# 1_Power_Switches.net
KiCad netlist of a schematic drawn in Altium Designer
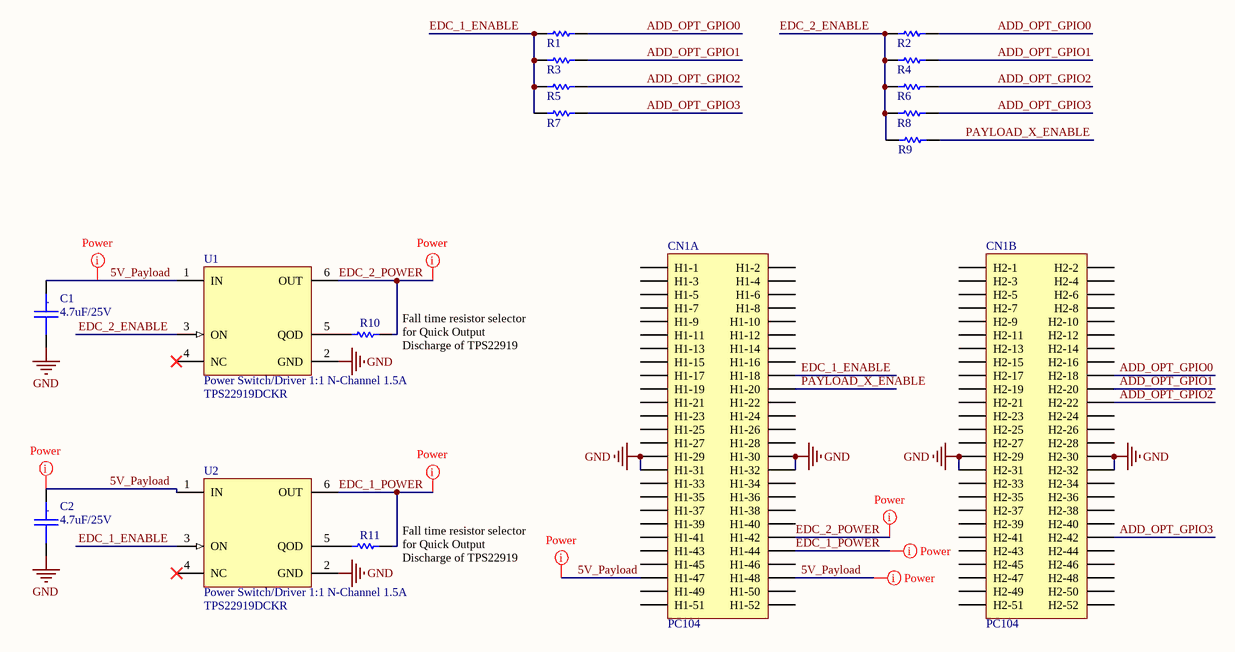
[diagram p0: 1_Power_Switches.SchDoc]

(export (version "E")
  (design (tool "Eeschema 10.0.6"))
  (components
    (comp (ref "C1")
      (value "4.7uF/25V")
      (footprint "C0805_MD")
      (fields
        (field (name "MANUFACTURER") "TDK")
        (field (name "MANUFACTURER PART NUMBER") "C2012X7R1E475K125AB")
        (field (name "TOLERANCE") "10%")
      )
      (libsource (lib "EDC_Power_Adapter") (part "C2012X7R1E475K125AB"))
    )
    (comp (ref "C2")
      (value "4.7uF/25V")
      (footprint "C0805_MD")
      (fields
        (field (name "MANUFACTURER") "TDK")
        (field (name "MANUFACTURER PART NUMBER") "C2012X7R1E475K125AB")
        (field (name "TOLERANCE") "10%")
      )
      (libsource (lib "EDC_Power_Adapter") (part "C2012X7R1E475K125AB"))
    )
    (comp (ref "CN1")
      (value "PC104")
      (footprint "PC104_ESQ-126-39-G-D")
      (description "Conn Elevated Socket SKT 52 POS 2.54mm Solder ST Thru-Hole Tube")
      (fields (field (name "PARTNUMBER") "ESQ-126-39-G-D") (field (name "MANUFACTURER") "Samtec"))
      (libsource (lib "EDC_Power_Adapter") (part "PC104_ESQ-126-39-G-D"))
    )
    (comp (ref "R1")
      (value "Optional 0805 resistor")
      (footprint "R0805_MD")
      (fields
        (field (name "MANUFACTURER") "Vishay")
        (field (name "MANUFACTURER PART NUMBER") "CRCW08050000Z0EA")
        (field (name "TOLERANCE") "1%")
      )
      (libsource (lib "EDC_Power_Adapter") (part "CRCW08050000Z0EA"))
    )
    (comp (ref "R2")
      (value "Optional 0805 resistor")
      (footprint "R0805_MD")
      (fields
        (field (name "MANUFACTURER") "Vishay")
        (field (name "MANUFACTURER PART NUMBER") "CRCW08050000Z0EA")
        (field (name "TOLERANCE") "1%")
      )
      (libsource (lib "EDC_Power_Adapter") (part "CRCW08050000Z0EA"))
    )
    (comp (ref "R3")
      (value "Optional 0805 resistor")
      (footprint "R0805_MD")
      (fields
        (field (name "MANUFACTURER") "Vishay")
        (field (name "MANUFACTURER PART NUMBER") "CRCW08050000Z0EA")
        (field (name "TOLERANCE") "1%")
      )
      (libsource (lib "EDC_Power_Adapter") (part "CRCW08050000Z0EA"))
    )
    (comp (ref "R4")
      (value "Optional 0805 resistor")
      (footprint "R0805_MD")
      (fields
        (field (name "MANUFACTURER") "Vishay")
        (field (name "MANUFACTURER PART NUMBER") "CRCW08050000Z0EA")
        (field (name "TOLERANCE") "1%")
      )
      (libsource (lib "EDC_Power_Adapter") (part "CRCW08050000Z0EA"))
    )
    (comp (ref "R5")
      (value "Optional 0805 resistor")
      (footprint "R0805_MD")
      (fields
        (field (name "MANUFACTURER") "Vishay")
        (field (name "MANUFACTURER PART NUMBER") "CRCW08050000Z0EA")
        (field (name "TOLERANCE") "1%")
      )
      (libsource (lib "EDC_Power_Adapter") (part "CRCW08050000Z0EA"))
    )
    (comp (ref "R6")
      (value "Optional 0805 resistor")
      (footprint "R0805_MD")
      (fields
        (field (name "MANUFACTURER") "Vishay")
        (field (name "MANUFACTURER PART NUMBER") "CRCW08050000Z0EA")
        (field (name "TOLERANCE") "1%")
      )
      (libsource (lib "EDC_Power_Adapter") (part "CRCW08050000Z0EA"))
    )
    (comp (ref "R7")
      (value "Optional 0805 resistor")
      (footprint "R0805_MD")
      (fields
        (field (name "MANUFACTURER") "Vishay")
        (field (name "MANUFACTURER PART NUMBER") "CRCW08050000Z0EA")
        (field (name "TOLERANCE") "1%")
      )
      (libsource (lib "EDC_Power_Adapter") (part "CRCW08050000Z0EA"))
    )
    (comp (ref "R8")
      (value "Optional 0805 resistor")
      (footprint "R0805_MD")
      (fields
        (field (name "MANUFACTURER") "Vishay")
        (field (name "MANUFACTURER PART NUMBER") "CRCW08050000Z0EA")
        (field (name "TOLERANCE") "1%")
      )
      (libsource (lib "EDC_Power_Adapter") (part "CRCW08050000Z0EA"))
    )
    (comp (ref "R9")
      (value "Optional 0805 resistor")
      (footprint "R0805_MD")
      (fields
        (field (name "MANUFACTURER") "Vishay")
        (field (name "MANUFACTURER PART NUMBER") "CRCW08050000Z0EA")
        (field (name "TOLERANCE") "1%")
      )
      (libsource (lib "EDC_Power_Adapter") (part "CRCW08050000Z0EA"))
    )
    (comp (ref "R10")
      (value "Optional 0805 resistor")
      (footprint "R0805_MD")
      (fields
        (field (name "MANUFACTURER") "Vishay")
        (field (name "MANUFACTURER PART NUMBER") "CRCW08050000Z0EA")
        (field (name "TOLERANCE") "1%")
      )
      (libsource (lib "EDC_Power_Adapter") (part "CRCW08050000Z0EA"))
    )
    (comp (ref "R11")
      (value "Optional 0805 resistor")
      (footprint "R0805_MD")
      (fields
        (field (name "MANUFACTURER") "Vishay")
        (field (name "MANUFACTURER PART NUMBER") "CRCW08050000Z0EA")
        (field (name "TOLERANCE") "1%")
      )
      (libsource (lib "EDC_Power_Adapter") (part "CRCW08050000Z0EA"))
    )
    (comp (ref "U1")
      (value "Power Switch/Driver 1:1 N-Channel 1.5A")
      (footprint "6-TSSOP, SC-88, SOT-363")
      (description "5.5-V, 1.5-A, 90-mΩ load switch with adj. output discharge 6-SC70 -40 to 105")
      (fields
        (field (name "MANUFACTURER") "Texas Instruments")
        (field (name "MANUFACTURER PART NUMBER") "TPS22919DCKR")
      )
      (libsource (lib "EDC_Power_Adapter") (part "TPS22919DCKR"))
    )
    (comp (ref "U2")
      (value "Power Switch/Driver 1:1 N-Channel 1.5A")
      (footprint "6-TSSOP, SC-88, SOT-363")
      (description "5.5-V, 1.5-A, 90-mΩ load switch with adj. output discharge 6-SC70 -40 to 105")
      (fields
        (field (name "MANUFACTURER") "Texas Instruments")
        (field (name "MANUFACTURER PART NUMBER") "TPS22919DCKR")
      )
      (libsource (lib "EDC_Power_Adapter") (part "TPS22919DCKR"))
    )
  )
  (nets
    (net (code "1") (name "/5V_Payload") (class "Default")
      (node (ref "C1") (pin "1") (pinfunction "1_1") (pintype "passive"))
      (node (ref "C2") (pin "1") (pinfunction "1_1") (pintype "passive"))
      (node (ref "CN1") (pin "H1-47") (pinfunction "H1-47_H1-47") (pintype "passive"))
      (node (ref "CN1") (pin "H1-48") (pinfunction "H1-48_H1-48") (pintype "passive"))
      (node (ref "U1") (pin "1") (pinfunction "IN_1") (pintype "passive"))
      (node (ref "U2") (pin "1") (pinfunction "IN_1") (pintype "passive"))
    )
    (net (code "2") (name "/ADD_OPT_GPIO0") (class "Default")
      (node (ref "CN1") (pin "H2-18") (pinfunction "H2-18_H2-18") (pintype "passive"))
      (node (ref "R1") (pin "1") (pinfunction "1_1") (pintype "passive"))
      (node (ref "R2") (pin "1") (pinfunction "1_1") (pintype "passive"))
    )
    (net (code "3") (name "/ADD_OPT_GPIO1") (class "Default")
      (node (ref "CN1") (pin "H2-20") (pinfunction "H2-20_H2-20") (pintype "passive"))
      (node (ref "R3") (pin "1") (pinfunction "1_1") (pintype "passive"))
      (node (ref "R4") (pin "1") (pinfunction "1_1") (pintype "passive"))
    )
    (net (code "4") (name "/ADD_OPT_GPIO2") (class "Default")
      (node (ref "CN1") (pin "H2-22") (pinfunction "H2-22_H2-22") (pintype "passive"))
      (node (ref "R5") (pin "1") (pinfunction "1_1") (pintype "passive"))
      (node (ref "R6") (pin "1") (pinfunction "1_1") (pintype "passive"))
    )
    (net (code "5") (name "/ADD_OPT_GPIO3") (class "Default")
      (node (ref "CN1") (pin "H2-42") (pinfunction "H2-42_H2-42") (pintype "passive"))
      (node (ref "R7") (pin "1") (pinfunction "1_1") (pintype "passive"))
      (node (ref "R8") (pin "1") (pinfunction "1_1") (pintype "passive"))
    )
    (net (code "6") (name "/EDC_1_ENABLE") (class "Default")
      (node (ref "CN1") (pin "H1-18") (pinfunction "H1-18_H1-18") (pintype "passive"))
      (node (ref "R1") (pin "2") (pinfunction "2_2") (pintype "passive"))
      (node (ref "R3") (pin "2") (pinfunction "2_2") (pintype "passive"))
      (node (ref "R5") (pin "2") (pinfunction "2_2") (pintype "passive"))
      (node (ref "R7") (pin "2") (pinfunction "2_2") (pintype "passive"))
      (node (ref "U2") (pin "3") (pinfunction "ON_3") (pintype "input"))
    )
    (net (code "7") (name "/EDC_1_POWER") (class "Default")
      (node (ref "CN1") (pin "H1-44") (pinfunction "H1-44_H1-44") (pintype "passive"))
      (node (ref "R11") (pin "1") (pinfunction "1_1") (pintype "passive"))
      (node (ref "U2") (pin "6") (pinfunction "OUT_6") (pintype "passive"))
    )
    (net (code "8") (name "/EDC_2_ENABLE") (class "Default")
      (node (ref "R2") (pin "2") (pinfunction "2_2") (pintype "passive"))
      (node (ref "R4") (pin "2") (pinfunction "2_2") (pintype "passive"))
      (node (ref "R6") (pin "2") (pinfunction "2_2") (pintype "passive"))
      (node (ref "R8") (pin "2") (pinfunction "2_2") (pintype "passive"))
      (node (ref "R9") (pin "2") (pinfunction "2_2") (pintype "passive"))
      (node (ref "U1") (pin "3") (pinfunction "ON_3") (pintype "input"))
    )
    (net (code "9") (name "/EDC_2_POWER") (class "Default")
      (node (ref "CN1") (pin "H1-42") (pinfunction "H1-42_H1-42") (pintype "passive"))
      (node (ref "R10") (pin "1") (pinfunction "1_1") (pintype "passive"))
      (node (ref "U1") (pin "6") (pinfunction "OUT_6") (pintype "passive"))
    )
    (net (code "10") (name "/PAYLOAD_X_ENABLE") (class "Default")
      (node (ref "CN1") (pin "H1-20") (pinfunction "H1-20_H1-20") (pintype "passive"))
      (node (ref "R9") (pin "1") (pinfunction "1_1") (pintype "passive"))
    )
    (net (code "11") (name "GND") (class "Default")
      (node (ref "C1") (pin "2") (pinfunction "2_2") (pintype "passive"))
      (node (ref "C2") (pin "2") (pinfunction "2_2") (pintype "passive"))
      (node (ref "CN1") (pin "H1-29") (pinfunction "H1-29_H1-29") (pintype "passive"))
      (node (ref "CN1") (pin "H1-30") (pinfunction "H1-30_H1-30") (pintype "passive"))
      (node (ref "CN1") (pin "H1-31") (pinfunction "H1-31_H1-31") (pintype "passive"))
      (node (ref "CN1") (pin "H1-32") (pinfunction "H1-32_H1-32") (pintype "passive"))
      (node (ref "CN1") (pin "H2-29") (pinfunction "H2-29_H2-29") (pintype "passive"))
      (node (ref "CN1") (pin "H2-30") (pinfunction "H2-30_H2-30") (pintype "passive"))
      (node (ref "CN1") (pin "H2-31") (pinfunction "H2-31_H2-31") (pintype "passive"))
      (node (ref "U1") (pin "2") (pinfunction "GND_2") (pintype "passive"))
      (node (ref "U2") (pin "2") (pinfunction "GND_2") (pintype "passive"))
    )
    (net (code "12") (name "Net-(U1-QOD)") (class "Default")
      (node (ref "R10") (pin "2") (pinfunction "2_2") (pintype "passive"))
      (node (ref "U1") (pin "5") (pinfunction "QOD_5") (pintype "passive"))
    )
    (net (code "13") (name "Net-(U2-QOD)") (class "Default")
      (node (ref "R11") (pin "2") (pinfunction "2_2") (pintype "passive"))
      (node (ref "U2") (pin "5") (pinfunction "QOD_5") (pintype "passive"))
    )
    (net (code "14") (name "unconnected-(CN1-PadH1-1)") (class "Default")
      (node (ref "CN1") (pin "H1-1") (pinfunction "H1-1_H1-1") (pintype "passive"))
    )
    (net (code "15") (name "unconnected-(CN1-PadH1-2)") (class "Default")
      (node (ref "CN1") (pin "H1-2") (pinfunction "H1-2_H1-2") (pintype "passive"))
    )
    (net (code "16") (name "unconnected-(CN1-PadH1-3)") (class "Default")
      (node (ref "CN1") (pin "H1-3") (pinfunction "H1-3_H1-3") (pintype "passive"))
    )
    (net (code "17") (name "unconnected-(CN1-PadH1-4)") (class "Default")
      (node (ref "CN1") (pin "H1-4") (pinfunction "H1-4_H1-4") (pintype "passive"))
    )
    (net (code "18") (name "unconnected-(CN1-PadH1-5)") (class "Default")
      (node (ref "CN1") (pin "H1-5") (pinfunction "H1-5_H1-5") (pintype "passive"))
    )
    (net (code "19") (name "unconnected-(CN1-PadH1-6)") (class "Default")
      (node (ref "CN1") (pin "H1-6") (pinfunction "H1-6_H1-6") (pintype "passive"))
    )
    (net (code "20") (name "unconnected-(CN1-PadH1-7)") (class "Default")
      (node (ref "CN1") (pin "H1-7") (pinfunction "H1-7_H1-7") (pintype "passive"))
    )
    (net (code "21") (name "unconnected-(CN1-PadH1-8)") (class "Default")
      (node (ref "CN1") (pin "H1-8") (pinfunction "H1-8_H1-8") (pintype "passive"))
    )
    (net (code "22") (name "unconnected-(CN1-PadH1-9)") (class "Default")
      (node (ref "CN1") (pin "H1-9") (pinfunction "H1-9_H1-9") (pintype "passive"))
    )
    (net (code "23") (name "unconnected-(CN1-PadH1-10)") (class "Default")
      (node (ref "CN1") (pin "H1-10") (pinfunction "H1-10_H1-10") (pintype "passive"))
    )
    (net (code "24") (name "unconnected-(CN1-PadH1-11)") (class "Default")
      (node (ref "CN1") (pin "H1-11") (pinfunction "H1-11_H1-11") (pintype "passive"))
    )
    (net (code "25") (name "unconnected-(CN1-PadH1-12)") (class "Default")
      (node (ref "CN1") (pin "H1-12") (pinfunction "H1-12_H1-12") (pintype "passive"))
    )
    (net (code "26") (name "unconnected-(CN1-PadH1-13)") (class "Default")
      (node (ref "CN1") (pin "H1-13") (pinfunction "H1-13_H1-13") (pintype "passive"))
    )
    (net (code "27") (name "unconnected-(CN1-PadH1-14)") (class "Default")
      (node (ref "CN1") (pin "H1-14") (pinfunction "H1-14_H1-14") (pintype "passive"))
    )
    (net (code "28") (name "unconnected-(CN1-PadH1-15)") (class "Default")
      (node (ref "CN1") (pin "H1-15") (pinfunction "H1-15_H1-15") (pintype "passive"))
    )
    (net (code "29") (name "unconnected-(CN1-PadH1-16)") (class "Default")
      (node (ref "CN1") (pin "H1-16") (pinfunction "H1-16_H1-16") (pintype "passive"))
    )
    (net (code "30") (name "unconnected-(CN1-PadH1-17)") (class "Default")
      (node (ref "CN1") (pin "H1-17") (pinfunction "H1-17_H1-17") (pintype "passive"))
    )
    (net (code "31") (name "unconnected-(CN1-PadH1-19)") (class "Default")
      (node (ref "CN1") (pin "H1-19") (pinfunction "H1-19_H1-19") (pintype "passive"))
    )
    (net (code "32") (name "unconnected-(CN1-PadH1-21)") (class "Default")
      (node (ref "CN1") (pin "H1-21") (pinfunction "H1-21_H1-21") (pintype "passive"))
    )
    (net (code "33") (name "unconnected-(CN1-PadH1-22)") (class "Default")
      (node (ref "CN1") (pin "H1-22") (pinfunction "H1-22_H1-22") (pintype "passive"))
    )
    (net (code "34") (name "unconnected-(CN1-PadH1-23)") (class "Default")
      (node (ref "CN1") (pin "H1-23") (pinfunction "H1-23_H1-23") (pintype "passive"))
    )
    (net (code "35") (name "unconnected-(CN1-PadH1-24)") (class "Default")
      (node (ref "CN1") (pin "H1-24") (pinfunction "H1-24_H1-24") (pintype "passive"))
    )
    (net (code "36") (name "unconnected-(CN1-PadH1-25)") (class "Default")
      (node (ref "CN1") (pin "H1-25") (pinfunction "H1-25_H1-25") (pintype "passive"))
    )
    (net (code "37") (name "unconnected-(CN1-PadH1-26)") (class "Default")
      (node (ref "CN1") (pin "H1-26") (pinfunction "H1-26_H1-26") (pintype "passive"))
    )
    (net (code "38") (name "unconnected-(CN1-PadH1-27)") (class "Default")
      (node (ref "CN1") (pin "H1-27") (pinfunction "H1-27_H1-27") (pintype "passive"))
    )
    (net (code "39") (name "unconnected-(CN1-PadH1-28)") (class "Default")
      (node (ref "CN1") (pin "H1-28") (pinfunction "H1-28_H1-28") (pintype "passive"))
    )
    (net (code "40") (name "unconnected-(CN1-PadH1-33)") (class "Default")
      (node (ref "CN1") (pin "H1-33") (pinfunction "H1-33_H1-33") (pintype "passive"))
    )
    (net (code "41") (name "unconnected-(CN1-PadH1-34)") (class "Default")
      (node (ref "CN1") (pin "H1-34") (pinfunction "H1-34_H1-34") (pintype "passive"))
    )
    (net (code "42") (name "unconnected-(CN1-PadH1-35)") (class "Default")
      (node (ref "CN1") (pin "H1-35") (pinfunction "H1-35_H1-35") (pintype "passive"))
    )
    (net (code "43") (name "unconnected-(CN1-PadH1-36)") (class "Default")
      (node (ref "CN1") (pin "H1-36") (pinfunction "H1-36_H1-36") (pintype "passive"))
    )
    (net (code "44") (name "unconnected-(CN1-PadH1-37)") (class "Default")
      (node (ref "CN1") (pin "H1-37") (pinfunction "H1-37_H1-37") (pintype "passive"))
    )
    (net (code "45") (name "unconnected-(CN1-PadH1-38)") (class "Default")
      (node (ref "CN1") (pin "H1-38") (pinfunction "H1-38_H1-38") (pintype "passive"))
    )
    (net (code "46") (name "unconnected-(CN1-PadH1-39)") (class "Default")
      (node (ref "CN1") (pin "H1-39") (pinfunction "H1-39_H1-39") (pintype "passive"))
    )
    (net (code "47") (name "unconnected-(CN1-PadH1-40)") (class "Default")
      (node (ref "CN1") (pin "H1-40") (pinfunction "H1-40_H1-40") (pintype "passive"))
    )
    (net (code "48") (name "unconnected-(CN1-PadH1-41)") (class "Default")
      (node (ref "CN1") (pin "H1-41") (pinfunction "H1-41_H1-41") (pintype "passive"))
    )
    (net (code "49") (name "unconnected-(CN1-PadH1-43)") (class "Default")
      (node (ref "CN1") (pin "H1-43") (pinfunction "H1-43_H1-43") (pintype "passive"))
    )
    (net (code "50") (name "unconnected-(CN1-PadH1-45)") (class "Default")
      (node (ref "CN1") (pin "H1-45") (pinfunction "H1-45_H1-45") (pintype "passive"))
    )
    (net (code "51") (name "unconnected-(CN1-PadH1-46)") (class "Default")
      (node (ref "CN1") (pin "H1-46") (pinfunction "H1-46_H1-46") (pintype "passive"))
    )
    (net (code "52") (name "unconnected-(CN1-PadH1-49)") (class "Default")
      (node (ref "CN1") (pin "H1-49") (pinfunction "H1-49_H1-49") (pintype "passive"))
    )
    (net (code "53") (name "unconnected-(CN1-PadH1-50)") (class "Default")
      (node (ref "CN1") (pin "H1-50") (pinfunction "H1-50_H1-50") (pintype "passive"))
    )
    (net (code "54") (name "unconnected-(CN1-PadH1-51)") (class "Default")
      (node (ref "CN1") (pin "H1-51") (pinfunction "H1-51_H1-51") (pintype "passive"))
    )
    (net (code "55") (name "unconnected-(CN1-PadH1-52)") (class "Default")
      (node (ref "CN1") (pin "H1-52") (pinfunction "H1-52_H1-52") (pintype "passive"))
    )
    (net (code "56") (name "unconnected-(CN1-PadH2-1)") (class "Default")
      (node (ref "CN1") (pin "H2-1") (pinfunction "H2-1_H2-1") (pintype "passive"))
    )
    (net (code "57") (name "unconnected-(CN1-PadH2-2)") (class "Default")
      (node (ref "CN1") (pin "H2-2") (pinfunction "H2-2_H2-2") (pintype "passive"))
    )
    (net (code "58") (name "unconnected-(CN1-PadH2-3)") (class "Default")
      (node (ref "CN1") (pin "H2-3") (pinfunction "H2-3_H2-3") (pintype "passive"))
    )
    (net (code "59") (name "unconnected-(CN1-PadH2-4)") (class "Default")
      (node (ref "CN1") (pin "H2-4") (pinfunction "H2-4_H2-4") (pintype "passive"))
    )
    (net (code "60") (name "unconnected-(CN1-PadH2-5)") (class "Default")
      (node (ref "CN1") (pin "H2-5") (pinfunction "H2-5_H2-5") (pintype "passive"))
    )
    (net (code "61") (name "unconnected-(CN1-PadH2-6)") (class "Default")
      (node (ref "CN1") (pin "H2-6") (pinfunction "H2-6_H2-6") (pintype "passive"))
    )
    (net (code "62") (name "unconnected-(CN1-PadH2-7)") (class "Default")
      (node (ref "CN1") (pin "H2-7") (pinfunction "H2-7_H2-7") (pintype "passive"))
    )
    (net (code "63") (name "unconnected-(CN1-PadH2-8)") (class "Default")
      (node (ref "CN1") (pin "H2-8") (pinfunction "H2-8_H2-8") (pintype "passive"))
    )
    (net (code "64") (name "unconnected-(CN1-PadH2-9)") (class "Default")
      (node (ref "CN1") (pin "H2-9") (pinfunction "H2-9_H2-9") (pintype "passive"))
    )
    (net (code "65") (name "unconnected-(CN1-PadH2-10)") (class "Default")
      (node (ref "CN1") (pin "H2-10") (pinfunction "H2-10_H2-10") (pintype "passive"))
    )
    (net (code "66") (name "unconnected-(CN1-PadH2-11)") (class "Default")
      (node (ref "CN1") (pin "H2-11") (pinfunction "H2-11_H2-11") (pintype "passive"))
    )
    (net (code "67") (name "unconnected-(CN1-PadH2-12)") (class "Default")
      (node (ref "CN1") (pin "H2-12") (pinfunction "H2-12_H2-12") (pintype "passive"))
    )
    (net (code "68") (name "unconnected-(CN1-PadH2-13)") (class "Default")
      (node (ref "CN1") (pin "H2-13") (pinfunction "H2-13_H2-13") (pintype "passive"))
    )
    (net (code "69") (name "unconnected-(CN1-PadH2-14)") (class "Default")
      (node (ref "CN1") (pin "H2-14") (pinfunction "H2-14_H2-14") (pintype "passive"))
    )
    (net (code "70") (name "unconnected-(CN1-PadH2-15)") (class "Default")
      (node (ref "CN1") (pin "H2-15") (pinfunction "H2-15_H2-15") (pintype "passive"))
    )
    (net (code "71") (name "unconnected-(CN1-PadH2-16)") (class "Default")
      (node (ref "CN1") (pin "H2-16") (pinfunction "H2-16_H2-16") (pintype "passive"))
    )
    (net (code "72") (name "unconnected-(CN1-PadH2-17)") (class "Default")
      (node (ref "CN1") (pin "H2-17") (pinfunction "H2-17_H2-17") (pintype "passive"))
    )
    (net (code "73") (name "unconnected-(CN1-PadH2-19)") (class "Default")
      (node (ref "CN1") (pin "H2-19") (pinfunction "H2-19_H2-19") (pintype "passive"))
    )
    (net (code "74") (name "unconnected-(CN1-PadH2-21)") (class "Default")
      (node (ref "CN1") (pin "H2-21") (pinfunction "H2-21_H2-21") (pintype "passive"))
    )
    (net (code "75") (name "unconnected-(CN1-PadH2-23)") (class "Default")
      (node (ref "CN1") (pin "H2-23") (pinfunction "H2-23_H2-23") (pintype "passive"))
    )
    (net (code "76") (name "unconnected-(CN1-PadH2-24)") (class "Default")
      (node (ref "CN1") (pin "H2-24") (pinfunction "H2-24_H2-24") (pintype "passive"))
    )
    (net (code "77") (name "unconnected-(CN1-PadH2-25)") (class "Default")
      (node (ref "CN1") (pin "H2-25") (pinfunction "H2-25_H2-25") (pintype "passive"))
    )
    (net (code "78") (name "unconnected-(CN1-PadH2-26)") (class "Default")
      (node (ref "CN1") (pin "H2-26") (pinfunction "H2-26_H2-26") (pintype "passive"))
    )
    (net (code "79") (name "unconnected-(CN1-PadH2-27)") (class "Default")
      (node (ref "CN1") (pin "H2-27") (pinfunction "H2-27_H2-27") (pintype "passive"))
    )
    (net (code "80") (name "unconnected-(CN1-PadH2-28)") (class "Default")
      (node (ref "CN1") (pin "H2-28") (pinfunction "H2-28_H2-28") (pintype "passive"))
    )
    (net (code "81") (name "unconnected-(CN1-PadH2-33)") (class "Default")
      (node (ref "CN1") (pin "H2-33") (pinfunction "H2-33_H2-33") (pintype "passive"))
    )
    (net (code "82") (name "unconnected-(CN1-PadH2-34)") (class "Default")
      (node (ref "CN1") (pin "H2-34") (pinfunction "H2-34_H2-34") (pintype "passive"))
    )
    (net (code "83") (name "unconnected-(CN1-PadH2-35)") (class "Default")
      (node (ref "CN1") (pin "H2-35") (pinfunction "H2-35_H2-35") (pintype "passive"))
    )
    (net (code "84") (name "unconnected-(CN1-PadH2-36)") (class "Default")
      (node (ref "CN1") (pin "H2-36") (pinfunction "H2-36_H2-36") (pintype "passive"))
    )
    (net (code "85") (name "unconnected-(CN1-PadH2-37)") (class "Default")
      (node (ref "CN1") (pin "H2-37") (pinfunction "H2-37_H2-37") (pintype "passive"))
    )
    (net (code "86") (name "unconnected-(CN1-PadH2-38)") (class "Default")
      (node (ref "CN1") (pin "H2-38") (pinfunction "H2-38_H2-38") (pintype "passive"))
    )
    (net (code "87") (name "unconnected-(CN1-PadH2-39)") (class "Default")
      (node (ref "CN1") (pin "H2-39") (pinfunction "H2-39_H2-39") (pintype "passive"))
    )
    (net (code "88") (name "unconnected-(CN1-PadH2-40)") (class "Default")
      (node (ref "CN1") (pin "H2-40") (pinfunction "H2-40_H2-40") (pintype "passive"))
    )
    (net (code "89") (name "unconnected-(CN1-PadH2-41)") (class "Default")
      (node (ref "CN1") (pin "H2-41") (pinfunction "H2-41_H2-41") (pintype "passive"))
    )
    (net (code "90") (name "unconnected-(CN1-PadH2-43)") (class "Default")
      (node (ref "CN1") (pin "H2-43") (pinfunction "H2-43_H2-43") (pintype "passive"))
    )
    (net (code "91") (name "unconnected-(CN1-PadH2-44)") (class "Default")
      (node (ref "CN1") (pin "H2-44") (pinfunction "H2-44_H2-44") (pintype "passive"))
    )
    (net (code "92") (name "unconnected-(CN1-PadH2-45)") (class "Default")
      (node (ref "CN1") (pin "H2-45") (pinfunction "H2-45_H2-45") (pintype "passive"))
    )
    (net (code "93") (name "unconnected-(CN1-PadH2-46)") (class "Default")
      (node (ref "CN1") (pin "H2-46") (pinfunction "H2-46_H2-46") (pintype "passive"))
    )
    (net (code "94") (name "unconnected-(CN1-PadH2-47)") (class "Default")
      (node (ref "CN1") (pin "H2-47") (pinfunction "H2-47_H2-47") (pintype "passive"))
    )
    (net (code "95") (name "unconnected-(CN1-PadH2-48)") (class "Default")
      (node (ref "CN1") (pin "H2-48") (pinfunction "H2-48_H2-48") (pintype "passive"))
    )
    (net (code "96") (name "unconnected-(CN1-PadH2-49)") (class "Default")
      (node (ref "CN1") (pin "H2-49") (pinfunction "H2-49_H2-49") (pintype "passive"))
    )
    (net (code "97") (name "unconnected-(CN1-PadH2-50)") (class "Default")
      (node (ref "CN1") (pin "H2-50") (pinfunction "H2-50_H2-50") (pintype "passive"))
    )
    (net (code "98") (name "unconnected-(CN1-PadH2-51)") (class "Default")
      (node (ref "CN1") (pin "H2-51") (pinfunction "H2-51_H2-51") (pintype "passive"))
    )
    (net (code "99") (name "unconnected-(CN1-PadH2-52)") (class "Default")
      (node (ref "CN1") (pin "H2-52") (pinfunction "H2-52_H2-52") (pintype "passive"))
    )
    (net (code "100") (name "unconnected-(U1-NC-Pad4)") (class "Default")
      (node (ref "U1") (pin "4") (pinfunction "NC_4") (pintype "passive+no_connect"))
    )
    (net (code "101") (name "unconnected-(U2-NC-Pad4)") (class "Default")
      (node (ref "U2") (pin "4") (pinfunction "NC_4") (pintype "passive+no_connect"))
    )
  )
)
